# 5V-3v3.net
KiCad netlist of a schematic drawn in Altium Designer
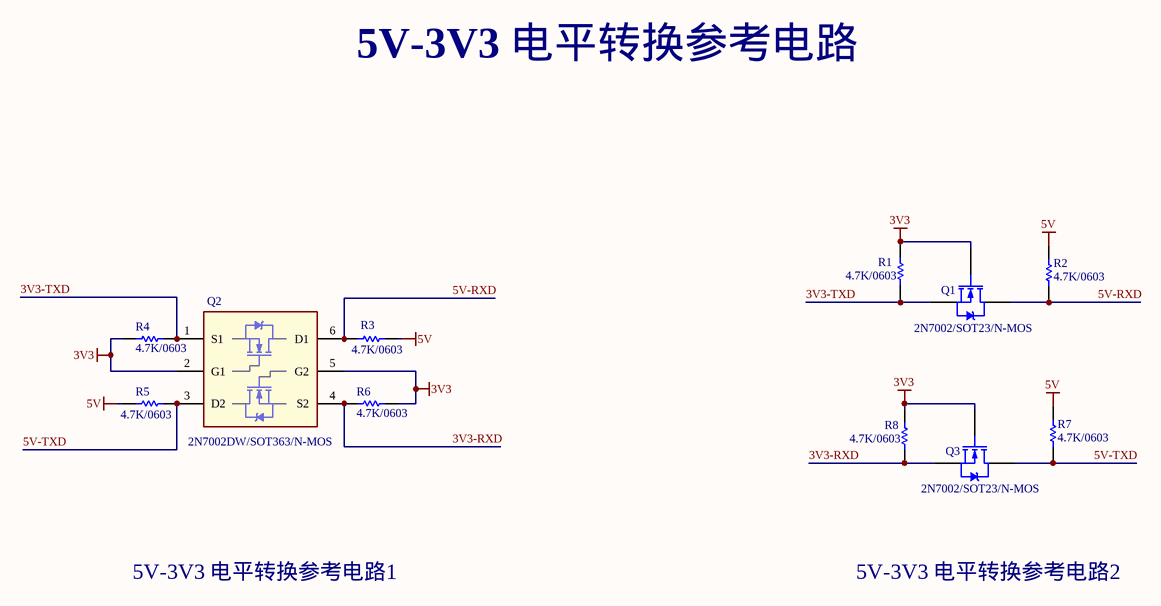
[diagram p0: 5V-3v3电平转换参考电路.SchDoc]

(export (version "E")
  (design (tool "Eeschema 10.0.6"))
  (components
    (comp (ref "Q1")
      (value "2N7002/SOT23/N-MOS")
      (footprint "SOT_23")
      (description "N-Channel Power MOSFET")
      (fields (field (name "PUBLISHER") "Altium Limited"))
      (libsource (lib "Miscellaneous Devices") (part "NMOS-2"))
    )
    (comp (ref "Q2")
      (value "2N7002DW/SOT363/N-MOS")
      (footprint "SOT363")
      (description "N-Channel Power MOSFET")
      (fields (field (name "PUBLISHER") "Altium Limited"))
      (libsource (lib "HEKR_2G") (part "2N7002DW"))
    )
    (comp (ref "Q3")
      (value "2N7002/SOT23/N-MOS")
      (footprint "SOT_23")
      (description "N-Channel Power MOSFET")
      (fields (field (name "PUBLISHER") "Altium Limited"))
      (libsource (lib "Miscellaneous Devices") (part "NMOS-2"))
    )
    (comp (ref "R1")
      (value "4.7K/0603")
      (footprint "R_0603")
      (description "Resistor")
      (fields (field (name "PUBLISHER") "Altium Limited"))
      (libsource (lib "Miscellaneous Devices") (part "Res1"))
    )
    (comp (ref "R2")
      (value "4.7K/0603")
      (footprint "R_0603")
      (description "Resistor")
      (fields (field (name "PUBLISHER") "Altium Limited"))
      (libsource (lib "Miscellaneous Devices") (part "Res1"))
    )
    (comp (ref "R3")
      (value "4.7K/0603")
      (footprint "R_0402")
      (description "Resistor")
      (fields (field (name "PUBLISHER") "Altium Limited"))
      (libsource (lib "Miscellaneous Devices") (part "Res1"))
    )
    (comp (ref "R4")
      (value "4.7K/0603")
      (footprint "R_0402")
      (description "Resistor")
      (fields (field (name "PUBLISHER") "Altium Limited"))
      (libsource (lib "Miscellaneous Devices") (part "Res1"))
    )
    (comp (ref "R5")
      (value "4.7K/0603")
      (footprint "R_0402")
      (description "Resistor")
      (fields (field (name "PUBLISHER") "Altium Limited"))
      (libsource (lib "Miscellaneous Devices") (part "Res1"))
    )
    (comp (ref "R6")
      (value "4.7K/0603")
      (footprint "R_0402")
      (description "Resistor")
      (fields (field (name "PUBLISHER") "Altium Limited"))
      (libsource (lib "Miscellaneous Devices") (part "Res1"))
    )
    (comp (ref "R7")
      (value "4.7K/0603")
      (footprint "R_0603")
      (description "Resistor")
      (fields (field (name "PUBLISHER") "Altium Limited"))
      (libsource (lib "Miscellaneous Devices") (part "Res1"))
    )
    (comp (ref "R8")
      (value "4.7K/0603")
      (footprint "R_0603")
      (description "Resistor")
      (fields (field (name "PUBLISHER") "Altium Limited"))
      (libsource (lib "Miscellaneous Devices") (part "Res1"))
    )
  )
  (nets
    (net (code "1") (name "/3V3-RXD") (class "Default")
      (node (ref "Q2") (pin "4") (pinfunction "S2_4") (pintype "passive"))
      (node (ref "Q3") (pin "2") (pinfunction "S_2") (pintype "passive"))
      (node (ref "R6") (pin "1") (pinfunction "1_1") (pintype "passive"))
      (node (ref "R8") (pin "2") (pinfunction "2_2") (pintype "passive"))
    )
    (net (code "2") (name "/3V3-TXD") (class "Default")
      (node (ref "Q1") (pin "2") (pinfunction "S_2") (pintype "passive"))
      (node (ref "Q2") (pin "1") (pinfunction "S1_1") (pintype "passive"))
      (node (ref "R1") (pin "2") (pinfunction "2_2") (pintype "passive"))
      (node (ref "R4") (pin "2") (pinfunction "2_2") (pintype "passive"))
    )
    (net (code "3") (name "/5V-RXD") (class "Default")
      (node (ref "Q1") (pin "3") (pinfunction "D_3") (pintype "passive"))
      (node (ref "Q2") (pin "6") (pinfunction "D1_6") (pintype "passive"))
      (node (ref "R2") (pin "2") (pinfunction "2_2") (pintype "passive"))
      (node (ref "R3") (pin "1") (pinfunction "1_1") (pintype "passive"))
    )
    (net (code "4") (name "/5V-TXD") (class "Default")
      (node (ref "Q2") (pin "3") (pinfunction "D2_3") (pintype "passive"))
      (node (ref "Q3") (pin "3") (pinfunction "D_3") (pintype "passive"))
      (node (ref "R5") (pin "2") (pinfunction "2_2") (pintype "passive"))
      (node (ref "R7") (pin "2") (pinfunction "2_2") (pintype "passive"))
    )
    (net (code "5") (name "3V3") (class "Default")
      (node (ref "Q1") (pin "1") (pinfunction "G_1") (pintype "passive"))
      (node (ref "Q2") (pin "2") (pinfunction "G1_2") (pintype "passive"))
      (node (ref "Q2") (pin "5") (pinfunction "G2_5") (pintype "passive"))
      (node (ref "Q3") (pin "1") (pinfunction "G_1") (pintype "passive"))
      (node (ref "R1") (pin "1") (pinfunction "1_1") (pintype "passive"))
      (node (ref "R4") (pin "1") (pinfunction "1_1") (pintype "passive"))
      (node (ref "R6") (pin "2") (pinfunction "2_2") (pintype "passive"))
      (node (ref "R8") (pin "1") (pinfunction "1_1") (pintype "passive"))
    )
    (net (code "6") (name "5V") (class "Default")
      (node (ref "R2") (pin "1") (pinfunction "1_1") (pintype "passive"))
      (node (ref "R3") (pin "2") (pinfunction "2_2") (pintype "passive"))
      (node (ref "R5") (pin "1") (pinfunction "1_1") (pintype "passive"))
      (node (ref "R7") (pin "1") (pinfunction "1_1") (pintype "passive"))
    )
  )
)
